# 01.net
KiCad netlist of a schematic drawn in Altium Designer
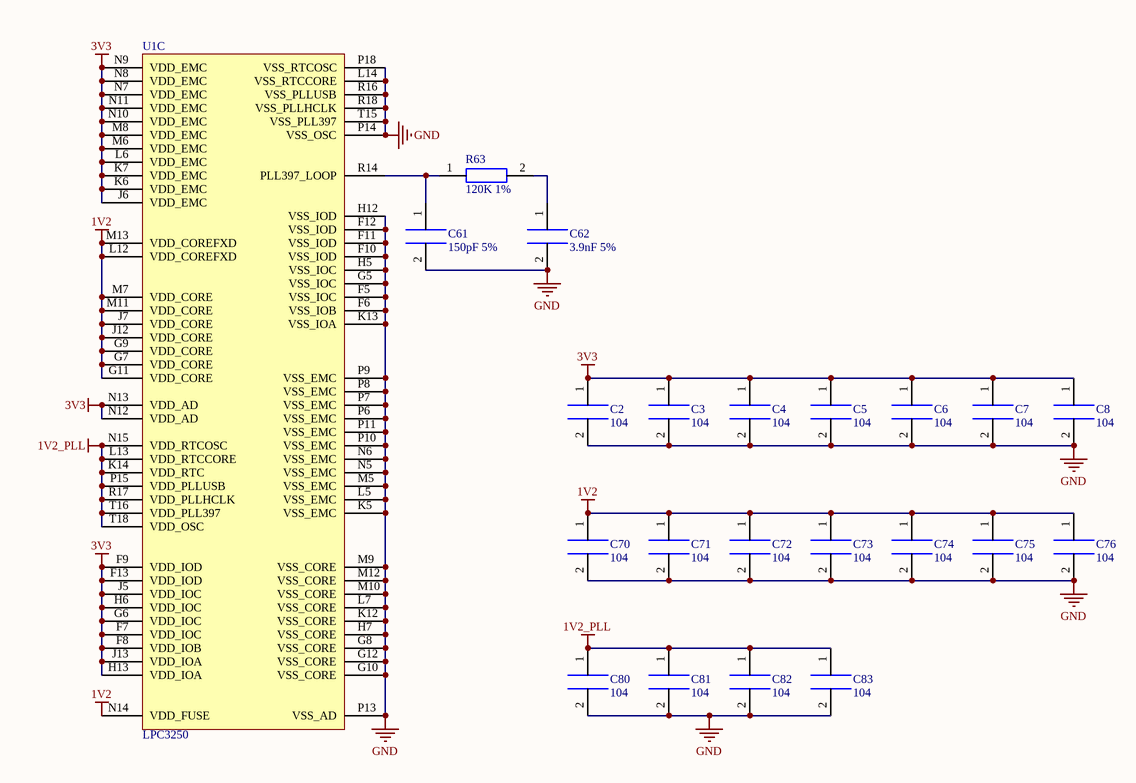
[diagram p0: 01.SchDoc]

(export (version "E")
  (design (tool "Eeschema 10.0.6"))
  (components
    (comp (ref "C2") (value "104") (footprint "0603C") (libsource (lib "MyProject1") (part "CAP")))
    (comp (ref "C3") (value "104") (footprint "0603C") (libsource (lib "MyProject1") (part "CAP")))
    (comp (ref "C4") (value "104") (footprint "0603C") (libsource (lib "MyProject1") (part "CAP")))
    (comp (ref "C5") (value "104") (footprint "0603C") (libsource (lib "MyProject1") (part "CAP")))
    (comp (ref "C6") (value "104") (footprint "0603C") (libsource (lib "MyProject1") (part "CAP")))
    (comp (ref "C7") (value "104") (footprint "0603C") (libsource (lib "MyProject1") (part "CAP")))
    (comp (ref "C8") (value "104") (footprint "0603C") (libsource (lib "MyProject1") (part "CAP")))
    (comp (ref "C61") (value "150pF 5%") (footprint "0603C") (libsource (lib "MyProject1") (part "CAP")))
    (comp (ref "C62") (value "3.9nF 5%") (footprint "0603C") (libsource (lib "MyProject1") (part "CAP")))
    (comp (ref "C70") (value "104") (footprint "0603C") (libsource (lib "MyProject1") (part "CAP")))
    (comp (ref "C71") (value "104") (footprint "0603C") (libsource (lib "MyProject1") (part "CAP")))
    (comp (ref "C72") (value "104") (footprint "0603C") (libsource (lib "MyProject1") (part "CAP")))
    (comp (ref "C73") (value "104") (footprint "0603C") (libsource (lib "MyProject1") (part "CAP")))
    (comp (ref "C74") (value "104") (footprint "0603C") (libsource (lib "MyProject1") (part "CAP")))
    (comp (ref "C75") (value "104") (footprint "0603C") (libsource (lib "MyProject1") (part "CAP")))
    (comp (ref "C76") (value "104") (footprint "0603C") (libsource (lib "MyProject1") (part "CAP")))
    (comp (ref "C80") (value "104") (footprint "0603C") (libsource (lib "MyProject1") (part "CAP")))
    (comp (ref "C81") (value "104") (footprint "0603C") (libsource (lib "MyProject1") (part "CAP")))
    (comp (ref "C82") (value "104") (footprint "0603C") (libsource (lib "MyProject1") (part "CAP")))
    (comp (ref "C83") (value "104") (footprint "0603C") (libsource (lib "MyProject1") (part "CAP")))
    (comp (ref "R63") (value "120K 1%") (footprint "0603R") (libsource (lib "MyProject1") (part "RES")))
    (comp (ref "U1") (value "LPC3250") (footprint "TFBGA296") (libsource (lib "MyProject1") (part "LPC3250")))
  )
  (nets
    (net (code "1") (name "1V2") (class "Default")
      (node (ref "C70") (pin "1") (pinfunction "1_1") (pintype "passive"))
      (node (ref "C71") (pin "1") (pinfunction "1_1") (pintype "passive"))
      (node (ref "C72") (pin "1") (pinfunction "1_1") (pintype "passive"))
      (node (ref "C73") (pin "1") (pinfunction "1_1") (pintype "passive"))
      (node (ref "C74") (pin "1") (pinfunction "1_1") (pintype "passive"))
      (node (ref "C75") (pin "1") (pinfunction "1_1") (pintype "passive"))
      (node (ref "C76") (pin "1") (pinfunction "1_1") (pintype "passive"))
      (node (ref "U1") (pin "G11") (pinfunction "VDD_CORE_G11") (pintype "passive"))
      (node (ref "U1") (pin "G7") (pinfunction "VDD_CORE_G7") (pintype "passive"))
      (node (ref "U1") (pin "G9") (pinfunction "VDD_CORE_G9") (pintype "passive"))
      (node (ref "U1") (pin "J12") (pinfunction "VDD_CORE_J12") (pintype "passive"))
      (node (ref "U1") (pin "J7") (pinfunction "VDD_CORE_J7") (pintype "passive"))
      (node (ref "U1") (pin "L12") (pinfunction "VDD_COREFXD_L12") (pintype "passive"))
      (node (ref "U1") (pin "M11") (pinfunction "VDD_CORE_M11") (pintype "passive"))
      (node (ref "U1") (pin "M13") (pinfunction "VDD_COREFXD_M13") (pintype "passive"))
      (node (ref "U1") (pin "M7") (pinfunction "VDD_CORE_M7") (pintype "passive"))
      (node (ref "U1") (pin "N14") (pinfunction "VDD_FUSE_N14") (pintype "passive"))
    )
    (net (code "2") (name "1V2_PLL") (class "Default")
      (node (ref "C80") (pin "1") (pinfunction "1_1") (pintype "passive"))
      (node (ref "C81") (pin "1") (pinfunction "1_1") (pintype "passive"))
      (node (ref "C82") (pin "1") (pinfunction "1_1") (pintype "passive"))
      (node (ref "C83") (pin "1") (pinfunction "1_1") (pintype "passive"))
      (node (ref "U1") (pin "K14") (pinfunction "VDD_RTC_K14") (pintype "passive"))
      (node (ref "U1") (pin "L13") (pinfunction "VDD_RTCCORE_L13") (pintype "passive"))
      (node (ref "U1") (pin "N15") (pinfunction "VDD_RTCOSC_N15") (pintype "passive"))
      (node (ref "U1") (pin "P15") (pinfunction "VDD_PLLUSB_P15") (pintype "passive"))
      (node (ref "U1") (pin "R17") (pinfunction "VDD_PLLHCLK_R17") (pintype "passive"))
      (node (ref "U1") (pin "T16") (pinfunction "VDD_PLL397_T16") (pintype "passive"))
      (node (ref "U1") (pin "T18") (pinfunction "VDD_OSC_T18") (pintype "passive"))
    )
    (net (code "3") (name "3V3") (class "Default")
      (node (ref "C2") (pin "1") (pinfunction "1_1") (pintype "passive"))
      (node (ref "C3") (pin "1") (pinfunction "1_1") (pintype "passive"))
      (node (ref "C4") (pin "1") (pinfunction "1_1") (pintype "passive"))
      (node (ref "C5") (pin "1") (pinfunction "1_1") (pintype "passive"))
      (node (ref "C6") (pin "1") (pinfunction "1_1") (pintype "passive"))
      (node (ref "C7") (pin "1") (pinfunction "1_1") (pintype "passive"))
      (node (ref "C8") (pin "1") (pinfunction "1_1") (pintype "passive"))
      (node (ref "U1") (pin "F13") (pinfunction "VDD_IOD_F13") (pintype "passive"))
      (node (ref "U1") (pin "F7") (pinfunction "VDD_IOC_F7") (pintype "passive"))
      (node (ref "U1") (pin "F8") (pinfunction "VDD_IOB_F8") (pintype "passive"))
      (node (ref "U1") (pin "F9") (pinfunction "VDD_IOD_F9") (pintype "passive"))
      (node (ref "U1") (pin "G6") (pinfunction "VDD_IOC_G6") (pintype "passive"))
      (node (ref "U1") (pin "H13") (pinfunction "VDD_IOA_H13") (pintype "passive"))
      (node (ref "U1") (pin "H6") (pinfunction "VDD_IOC_H6") (pintype "passive"))
      (node (ref "U1") (pin "J13") (pinfunction "VDD_IOA_J13") (pintype "passive"))
      (node (ref "U1") (pin "J5") (pinfunction "VDD_IOC_J5") (pintype "passive"))
      (node (ref "U1") (pin "J6") (pinfunction "VDD_EMC_J6") (pintype "passive"))
      (node (ref "U1") (pin "K6") (pinfunction "VDD_EMC_K6") (pintype "passive"))
      (node (ref "U1") (pin "K7") (pinfunction "VDD_EMC_K7") (pintype "passive"))
      (node (ref "U1") (pin "L6") (pinfunction "VDD_EMC_L6") (pintype "passive"))
      (node (ref "U1") (pin "M6") (pinfunction "VDD_EMC_M6") (pintype "passive"))
      (node (ref "U1") (pin "M8") (pinfunction "VDD_EMC_M8") (pintype "passive"))
      (node (ref "U1") (pin "N10") (pinfunction "VDD_EMC_N10") (pintype "passive"))
      (node (ref "U1") (pin "N11") (pinfunction "VDD_EMC_N11") (pintype "passive"))
      (node (ref "U1") (pin "N12") (pinfunction "VDD_AD_N12") (pintype "passive"))
      (node (ref "U1") (pin "N13") (pinfunction "VDD_AD_N13") (pintype "passive"))
      (node (ref "U1") (pin "N7") (pinfunction "VDD_EMC_N7") (pintype "passive"))
      (node (ref "U1") (pin "N8") (pinfunction "VDD_EMC_N8") (pintype "passive"))
      (node (ref "U1") (pin "N9") (pinfunction "VDD_EMC_N9") (pintype "passive"))
    )
    (net (code "4") (name "GND") (class "Default")
      (node (ref "C2") (pin "2") (pinfunction "2_2") (pintype "passive"))
      (node (ref "C3") (pin "2") (pinfunction "2_2") (pintype "passive"))
      (node (ref "C4") (pin "2") (pinfunction "2_2") (pintype "passive"))
      (node (ref "C5") (pin "2") (pinfunction "2_2") (pintype "passive"))
      (node (ref "C6") (pin "2") (pinfunction "2_2") (pintype "passive"))
      (node (ref "C61") (pin "2") (pinfunction "2_2") (pintype "passive"))
      (node (ref "C62") (pin "2") (pinfunction "2_2") (pintype "passive"))
      (node (ref "C7") (pin "2") (pinfunction "2_2") (pintype "passive"))
      (node (ref "C70") (pin "2") (pinfunction "2_2") (pintype "passive"))
      (node (ref "C71") (pin "2") (pinfunction "2_2") (pintype "passive"))
      (node (ref "C72") (pin "2") (pinfunction "2_2") (pintype "passive"))
      (node (ref "C73") (pin "2") (pinfunction "2_2") (pintype "passive"))
      (node (ref "C74") (pin "2") (pinfunction "2_2") (pintype "passive"))
      (node (ref "C75") (pin "2") (pinfunction "2_2") (pintype "passive"))
      (node (ref "C76") (pin "2") (pinfunction "2_2") (pintype "passive"))
      (node (ref "C8") (pin "2") (pinfunction "2_2") (pintype "passive"))
      (node (ref "C80") (pin "2") (pinfunction "2_2") (pintype "passive"))
      (node (ref "C81") (pin "2") (pinfunction "2_2") (pintype "passive"))
      (node (ref "C82") (pin "2") (pinfunction "2_2") (pintype "passive"))
      (node (ref "C83") (pin "2") (pinfunction "2_2") (pintype "passive"))
      (node (ref "U1") (pin "F10") (pinfunction "VSS_IOD_F10") (pintype "passive"))
      (node (ref "U1") (pin "F11") (pinfunction "VSS_IOD_F11") (pintype "passive"))
      (node (ref "U1") (pin "F12") (pinfunction "VSS_IOD_F12") (pintype "passive"))
      (node (ref "U1") (pin "F5") (pinfunction "VSS_IOC_F5") (pintype "passive"))
      (node (ref "U1") (pin "F6") (pinfunction "VSS_IOB_F6") (pintype "passive"))
      (node (ref "U1") (pin "G10") (pinfunction "VSS_CORE_G10") (pintype "passive"))
      (node (ref "U1") (pin "G12") (pinfunction "VSS_CORE_G12") (pintype "passive"))
      (node (ref "U1") (pin "G5") (pinfunction "VSS_IOC_G5") (pintype "passive"))
      (node (ref "U1") (pin "G8") (pinfunction "VSS_CORE_G8") (pintype "passive"))
      (node (ref "U1") (pin "H12") (pinfunction "VSS_IOD_H12") (pintype "passive"))
      (node (ref "U1") (pin "H5") (pinfunction "VSS_IOC_H5") (pintype "passive"))
      (node (ref "U1") (pin "H7") (pinfunction "VSS_CORE_H7") (pintype "passive"))
      (node (ref "U1") (pin "K12") (pinfunction "VSS_CORE_K12") (pintype "passive"))
      (node (ref "U1") (pin "K13") (pinfunction "VSS_IOA_K13") (pintype "passive"))
      (node (ref "U1") (pin "K5") (pinfunction "VSS_EMC_K5") (pintype "passive"))
      (node (ref "U1") (pin "L14") (pinfunction "VSS_RTCCORE_L14") (pintype "passive"))
      (node (ref "U1") (pin "L5") (pinfunction "VSS_EMC_L5") (pintype "passive"))
      (node (ref "U1") (pin "L7") (pinfunction "VSS_CORE_L7") (pintype "passive"))
      (node (ref "U1") (pin "M10") (pinfunction "VSS_CORE_M10") (pintype "passive"))
      (node (ref "U1") (pin "M12") (pinfunction "VSS_CORE_M12") (pintype "passive"))
      (node (ref "U1") (pin "M5") (pinfunction "VSS_EMC_M5") (pintype "passive"))
      (node (ref "U1") (pin "M9") (pinfunction "VSS_CORE_M9") (pintype "passive"))
      (node (ref "U1") (pin "N5") (pinfunction "VSS_EMC_N5") (pintype "passive"))
      (node (ref "U1") (pin "N6") (pinfunction "VSS_EMC_N6") (pintype "passive"))
      (node (ref "U1") (pin "P10") (pinfunction "VSS_EMC_P10") (pintype "passive"))
      (node (ref "U1") (pin "P11") (pinfunction "VSS_EMC_P11") (pintype "passive"))
      (node (ref "U1") (pin "P13") (pinfunction "VSS_AD_P13") (pintype "passive"))
      (node (ref "U1") (pin "P14") (pinfunction "VSS_OSC_P14") (pintype "passive"))
      (node (ref "U1") (pin "P18") (pinfunction "VSS_RTCOSC_P18") (pintype "passive"))
      (node (ref "U1") (pin "P6") (pinfunction "VSS_EMC_P6") (pintype "passive"))
      (node (ref "U1") (pin "P7") (pinfunction "VSS_EMC_P7") (pintype "passive"))
      (node (ref "U1") (pin "P8") (pinfunction "VSS_EMC_P8") (pintype "passive"))
      (node (ref "U1") (pin "P9") (pinfunction "VSS_EMC_P9") (pintype "passive"))
      (node (ref "U1") (pin "R16") (pinfunction "VSS_PLLUSB_R16") (pintype "passive"))
      (node (ref "U1") (pin "R18") (pinfunction "VSS_PLLHCLK_R18") (pintype "passive"))
      (node (ref "U1") (pin "T15") (pinfunction "VSS_PLL397_T15") (pintype "passive"))
    )
    (net (code "5") (name "Net-(C62-Pad1)") (class "Default")
      (node (ref "C62") (pin "1") (pinfunction "1_1") (pintype "passive"))
      (node (ref "R63") (pin "2") (pinfunction "2_2") (pintype "passive"))
    )
    (net (code "6") (name "Net-(U1C-PLL397_LOOP)") (class "Default")
      (node (ref "C61") (pin "1") (pinfunction "1_1") (pintype "passive"))
      (node (ref "R63") (pin "1") (pinfunction "1_1") (pintype "passive"))
      (node (ref "U1") (pin "R14") (pinfunction "PLL397_LOOP_R14") (pintype "passive"))
    )
  )
)
